# Remote.net
KiCad netlist of a schematic drawn in EAGLE
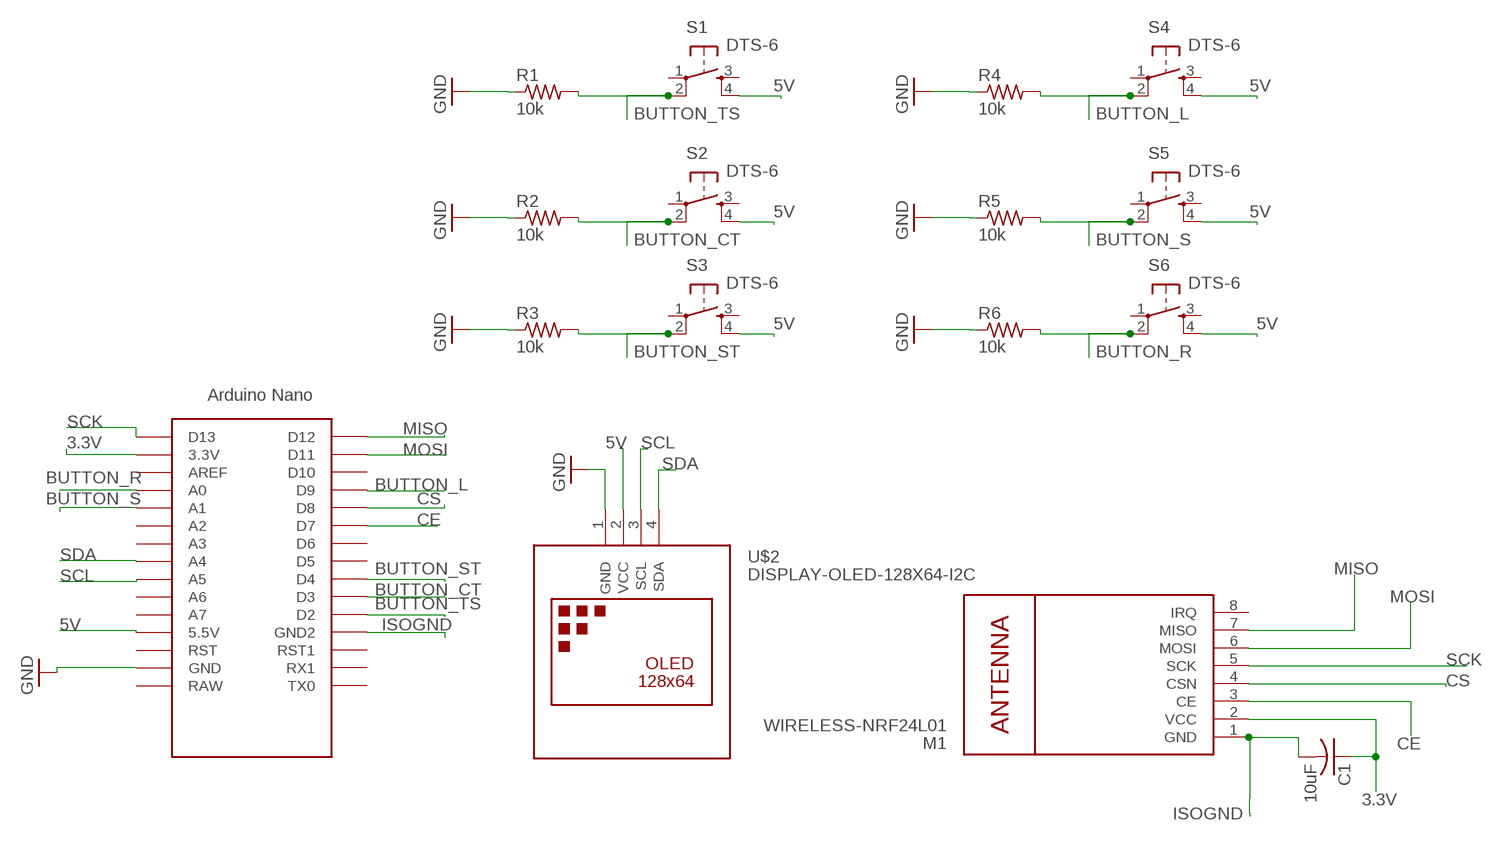
[diagram p0: schematic, sheet 1]

(export (version "E")
  (design (tool "Eeschema 10.0.6"))
  (components
    (comp (ref "C1")
      (value "10uF")
      (footprint "eagle-import:C025-030X050")
      (libsource (lib "eagle-import") (part "C-US025-030X050"))
    )
    (comp (ref "M1")
      (value "WIRELESS-NRF24L01")
      (footprint "eagle-import:WIRELESS-NRF24L01")
      (libsource (lib "eagle-import") (part "WIRELESS-NRF24L01"))
    )
    (comp (ref "R1")
      (value "10k")
      (footprint "eagle-import:0207_10")
      (libsource (lib "eagle-import") (part "R-US_0207/10"))
    )
    (comp (ref "R2")
      (value "10k")
      (footprint "eagle-import:0207_10")
      (libsource (lib "eagle-import") (part "R-US_0207/10"))
    )
    (comp (ref "R3")
      (value "10k")
      (footprint "eagle-import:0207_10")
      (libsource (lib "eagle-import") (part "R-US_0207/10"))
    )
    (comp (ref "R4")
      (value "10k")
      (footprint "eagle-import:0207_10")
      (libsource (lib "eagle-import") (part "R-US_0207/10"))
    )
    (comp (ref "R5")
      (value "10k")
      (footprint "eagle-import:0207_10")
      (libsource (lib "eagle-import") (part "R-US_0207/10"))
    )
    (comp (ref "R6")
      (value "10k")
      (footprint "eagle-import:0207_10")
      (libsource (lib "eagle-import") (part "R-US_0207/10"))
    )
    (comp (ref "S1")
      (value "DTS-6")
      (footprint "eagle-import:DTS-6")
      (libsource (lib "eagle-import") (part "DTS-6"))
    )
    (comp (ref "S2")
      (value "DTS-6")
      (footprint "eagle-import:DTS-6")
      (libsource (lib "eagle-import") (part "DTS-6"))
    )
    (comp (ref "S3")
      (value "DTS-6")
      (footprint "eagle-import:DTS-6")
      (libsource (lib "eagle-import") (part "DTS-6"))
    )
    (comp (ref "S4")
      (value "DTS-6")
      (footprint "eagle-import:DTS-6")
      (libsource (lib "eagle-import") (part "DTS-6"))
    )
    (comp (ref "S5")
      (value "DTS-6")
      (footprint "eagle-import:DTS-6")
      (libsource (lib "eagle-import") (part "DTS-6"))
    )
    (comp (ref "S6")
      (value "DTS-6")
      (footprint "eagle-import:DTS-6")
      (libsource (lib "eagle-import") (part "DTS-6"))
    )
    (comp (ref "U$1")
      (value "NANO")
      (footprint "eagle-import:NANO")
      (libsource (lib "eagle-import") (part "NANO"))
    )
    (comp (ref "U$2")
      (value "DISPLAY-OLED-128X64-I2C")
      (footprint "eagle-import:DISPLAY-OLED-128X64-I2C")
      (libsource (lib "eagle-import") (part "DISPLAY-OLED-128X64-I2C"))
    )
  )
  (nets
    (net (code "1") (name "/3.3V") (class "Default")
      (node (ref "C1") (pin "1") (pinfunction "1_1") (pintype "passive"))
      (node (ref "M1") (pin "2") (pinfunction "VCC_2") (pintype "power_in"))
      (node (ref "U$1") (pin "3.3V") (pinfunction "3.3V_3.3V") (pintype "bidirectional"))
    )
    (net (code "2") (name "/5V") (class "Default")
      (node (ref "S1") (pin "4") (pinfunction "4_4") (pintype "passive"))
      (node (ref "S2") (pin "4") (pinfunction "4_4") (pintype "passive"))
      (node (ref "S3") (pin "4") (pinfunction "4_4") (pintype "passive"))
      (node (ref "S4") (pin "4") (pinfunction "4_4") (pintype "passive"))
      (node (ref "S5") (pin "4") (pinfunction "4_4") (pintype "passive"))
      (node (ref "S6") (pin "4") (pinfunction "4_4") (pintype "passive"))
      (node (ref "U$1") (pin "5V") (pinfunction "5.5V_5V") (pintype "bidirectional"))
      (node (ref "U$2") (pin "2") (pinfunction "VCC_2") (pintype "power_in"))
    )
    (net (code "3") (name "/BUTTON_CT") (class "Default")
      (node (ref "R2") (pin "2") (pinfunction "2_2") (pintype "passive"))
      (node (ref "S2") (pin "2") (pinfunction "2_2") (pintype "passive"))
      (node (ref "U$1") (pin "D3") (pinfunction "D3_D3") (pintype "bidirectional"))
    )
    (net (code "4") (name "/BUTTON_L") (class "Default")
      (node (ref "R4") (pin "2") (pinfunction "2_2") (pintype "passive"))
      (node (ref "S4") (pin "2") (pinfunction "2_2") (pintype "passive"))
      (node (ref "U$1") (pin "D9") (pinfunction "D9_D9") (pintype "bidirectional"))
    )
    (net (code "5") (name "/BUTTON_R") (class "Default")
      (node (ref "R6") (pin "2") (pinfunction "2_2") (pintype "passive"))
      (node (ref "S6") (pin "2") (pinfunction "2_2") (pintype "passive"))
      (node (ref "U$1") (pin "A0") (pinfunction "A0_A0") (pintype "bidirectional"))
    )
    (net (code "6") (name "/BUTTON_S") (class "Default")
      (node (ref "R5") (pin "2") (pinfunction "2_2") (pintype "passive"))
      (node (ref "S5") (pin "2") (pinfunction "2_2") (pintype "passive"))
      (node (ref "U$1") (pin "A1") (pinfunction "A1_A1") (pintype "bidirectional"))
    )
    (net (code "7") (name "/BUTTON_ST") (class "Default")
      (node (ref "R3") (pin "2") (pinfunction "2_2") (pintype "passive"))
      (node (ref "S3") (pin "2") (pinfunction "2_2") (pintype "passive"))
      (node (ref "U$1") (pin "D4") (pinfunction "D4_D4") (pintype "bidirectional"))
    )
    (net (code "8") (name "/BUTTON_TS") (class "Default")
      (node (ref "R1") (pin "2") (pinfunction "2_2") (pintype "passive"))
      (node (ref "S1") (pin "2") (pinfunction "2_2") (pintype "passive"))
      (node (ref "U$1") (pin "D2") (pinfunction "D2_D2") (pintype "bidirectional"))
    )
    (net (code "9") (name "/CE") (class "Default")
      (node (ref "M1") (pin "3") (pinfunction "CE_3") (pintype "bidirectional"))
      (node (ref "U$1") (pin "D7") (pinfunction "D7_D7") (pintype "bidirectional"))
    )
    (net (code "10") (name "/CS") (class "Default")
      (node (ref "M1") (pin "4") (pinfunction "CSN_4") (pintype "bidirectional"))
      (node (ref "U$1") (pin "D8") (pinfunction "D8_D8") (pintype "bidirectional"))
    )
    (net (code "11") (name "/ISOGND") (class "Default")
      (node (ref "C1") (pin "2") (pinfunction "2_2") (pintype "passive"))
      (node (ref "M1") (pin "1") (pinfunction "GND_1") (pintype "power_in"))
      (node (ref "U$1") (pin "GND1") (pinfunction "GND2_GND1") (pintype "bidirectional"))
    )
    (net (code "12") (name "/MISO") (class "Default")
      (node (ref "M1") (pin "7") (pinfunction "MISO_7") (pintype "bidirectional"))
      (node (ref "U$1") (pin "D12") (pinfunction "D12_D12") (pintype "bidirectional"))
    )
    (net (code "13") (name "/MOSI") (class "Default")
      (node (ref "M1") (pin "6") (pinfunction "MOSI_6") (pintype "bidirectional"))
      (node (ref "U$1") (pin "D11") (pinfunction "D11_D11") (pintype "bidirectional"))
    )
    (net (code "14") (name "/SCK") (class "Default")
      (node (ref "M1") (pin "5") (pinfunction "SCK_5") (pintype "bidirectional"))
      (node (ref "U$1") (pin "D13") (pinfunction "D13_D13") (pintype "bidirectional"))
    )
    (net (code "15") (name "/SCL") (class "Default")
      (node (ref "U$1") (pin "A5") (pinfunction "A5_A5") (pintype "bidirectional"))
      (node (ref "U$2") (pin "3") (pinfunction "SCL_3") (pintype "bidirectional"))
    )
    (net (code "16") (name "/SDA") (class "Default")
      (node (ref "U$1") (pin "A4") (pinfunction "A4_A4") (pintype "bidirectional"))
      (node (ref "U$2") (pin "4") (pinfunction "SDA_4") (pintype "bidirectional"))
    )
    (net (code "17") (name "GND") (class "Default")
      (node (ref "R1") (pin "1") (pinfunction "1_1") (pintype "passive"))
      (node (ref "R2") (pin "1") (pinfunction "1_1") (pintype "passive"))
      (node (ref "R3") (pin "1") (pinfunction "1_1") (pintype "passive"))
      (node (ref "R4") (pin "1") (pinfunction "1_1") (pintype "passive"))
      (node (ref "R5") (pin "1") (pinfunction "1_1") (pintype "passive"))
      (node (ref "R6") (pin "1") (pinfunction "1_1") (pintype "passive"))
      (node (ref "U$1") (pin "GND") (pinfunction "GND_GND") (pintype "bidirectional"))
      (node (ref "U$2") (pin "1") (pinfunction "GND_1") (pintype "power_in"))
    )
    (net (code "18") (name "unconnected-(M1-IRQ-Pad8)") (class "Default")
      (node (ref "M1") (pin "8") (pinfunction "IRQ_8") (pintype "bidirectional"))
    )
    (net (code "19") (name "unconnected-(S1-Pad1)") (class "Default")
      (node (ref "S1") (pin "1") (pinfunction "1_1") (pintype "passive"))
    )
    (net (code "20") (name "unconnected-(S1-Pad3)") (class "Default")
      (node (ref "S1") (pin "3") (pinfunction "3_3") (pintype "passive"))
    )
    (net (code "21") (name "unconnected-(S2-Pad1)") (class "Default")
      (node (ref "S2") (pin "1") (pinfunction "1_1") (pintype "passive"))
    )
    (net (code "22") (name "unconnected-(S2-Pad3)") (class "Default")
      (node (ref "S2") (pin "3") (pinfunction "3_3") (pintype "passive"))
    )
    (net (code "23") (name "unconnected-(S3-Pad1)") (class "Default")
      (node (ref "S3") (pin "1") (pinfunction "1_1") (pintype "passive"))
    )
    (net (code "24") (name "unconnected-(S3-Pad3)") (class "Default")
      (node (ref "S3") (pin "3") (pinfunction "3_3") (pintype "passive"))
    )
    (net (code "25") (name "unconnected-(S4-Pad1)") (class "Default")
      (node (ref "S4") (pin "1") (pinfunction "1_1") (pintype "passive"))
    )
    (net (code "26") (name "unconnected-(S4-Pad3)") (class "Default")
      (node (ref "S4") (pin "3") (pinfunction "3_3") (pintype "passive"))
    )
    (net (code "27") (name "unconnected-(S5-Pad1)") (class "Default")
      (node (ref "S5") (pin "1") (pinfunction "1_1") (pintype "passive"))
    )
    (net (code "28") (name "unconnected-(S5-Pad3)") (class "Default")
      (node (ref "S5") (pin "3") (pinfunction "3_3") (pintype "passive"))
    )
    (net (code "29") (name "unconnected-(S6-Pad1)") (class "Default")
      (node (ref "S6") (pin "1") (pinfunction "1_1") (pintype "passive"))
    )
    (net (code "30") (name "unconnected-(S6-Pad3)") (class "Default")
      (node (ref "S6") (pin "3") (pinfunction "3_3") (pintype "passive"))
    )
    (net (code "31") (name "unconnected-(U$1-PadA2)") (class "Default")
      (node (ref "U$1") (pin "A2") (pinfunction "A2_A2") (pintype "bidirectional"))
    )
    (net (code "32") (name "unconnected-(U$1-PadA3)") (class "Default")
      (node (ref "U$1") (pin "A3") (pinfunction "A3_A3") (pintype "bidirectional"))
    )
    (net (code "33") (name "unconnected-(U$1-PadA6)") (class "Default")
      (node (ref "U$1") (pin "A6") (pinfunction "A6_A6") (pintype "bidirectional"))
    )
    (net (code "34") (name "unconnected-(U$1-PadA7)") (class "Default")
      (node (ref "U$1") (pin "A7") (pinfunction "A7_A7") (pintype "bidirectional"))
    )
    (net (code "35") (name "unconnected-(U$1-PadAREF)") (class "Default")
      (node (ref "U$1") (pin "AREF") (pinfunction "AREF_AREF") (pintype "bidirectional"))
    )
    (net (code "36") (name "unconnected-(U$1-PadD5)") (class "Default")
      (node (ref "U$1") (pin "D5") (pinfunction "D5_D5") (pintype "bidirectional"))
    )
    (net (code "37") (name "unconnected-(U$1-PadD6)") (class "Default")
      (node (ref "U$1") (pin "D6") (pinfunction "D6_D6") (pintype "bidirectional"))
    )
    (net (code "38") (name "unconnected-(U$1-PadD10)") (class "Default")
      (node (ref "U$1") (pin "D10") (pinfunction "D10_D10") (pintype "bidirectional"))
    )
    (net (code "39") (name "unconnected-(U$1-PadICSP1)") (class "Default")
      (node (ref "U$1") (pin "ICSP1") (pinfunction "ICSP1_ICSP1") (pintype "bidirectional"))
    )
    (net (code "40") (name "unconnected-(U$1-PadICSP2)") (class "Default")
      (node (ref "U$1") (pin "ICSP2") (pinfunction "ICSP2_ICSP2") (pintype "bidirectional"))
    )
    (net (code "41") (name "unconnected-(U$1-PadICSP3)") (class "Default")
      (node (ref "U$1") (pin "ICSP3") (pinfunction "ICSP3_ICSP3") (pintype "bidirectional"))
    )
    (net (code "42") (name "unconnected-(U$1-PadICSP4)") (class "Default")
      (node (ref "U$1") (pin "ICSP4") (pinfunction "ICSP4_ICSP4") (pintype "bidirectional"))
    )
    (net (code "43") (name "unconnected-(U$1-PadICSP5)") (class "Default")
      (node (ref "U$1") (pin "ICSP5") (pinfunction "ICSP5_ICSP5") (pintype "bidirectional"))
    )
    (net (code "44") (name "unconnected-(U$1-PadICSP6)") (class "Default")
      (node (ref "U$1") (pin "ICSP6") (pinfunction "ICSP6_ICSP6") (pintype "bidirectional"))
    )
    (net (code "45") (name "unconnected-(U$1-PadRAW)") (class "Default")
      (node (ref "U$1") (pin "RAW") (pinfunction "RAW_RAW") (pintype "bidirectional"))
    )
    (net (code "46") (name "unconnected-(U$1-PadRST)") (class "Default")
      (node (ref "U$1") (pin "RST") (pinfunction "RST_RST") (pintype "bidirectional"))
    )
    (net (code "47") (name "unconnected-(U$1-PadRST1)") (class "Default")
      (node (ref "U$1") (pin "RST1") (pinfunction "RST1_RST1") (pintype "bidirectional"))
    )
    (net (code "48") (name "unconnected-(U$1-PadRX1)") (class "Default")
      (node (ref "U$1") (pin "RX1") (pinfunction "RX1_RX1") (pintype "bidirectional"))
    )
    (net (code "49") (name "unconnected-(U$1-PadTX0)") (class "Default")
      (node (ref "U$1") (pin "TX0") (pinfunction "TX0_TX0") (pintype "bidirectional"))
    )
  )
)
